# SCH_Satlla_4_Solar_unit_left_2023-01-29.net
KiCad netlist of a schematic drawn in EasyEDA
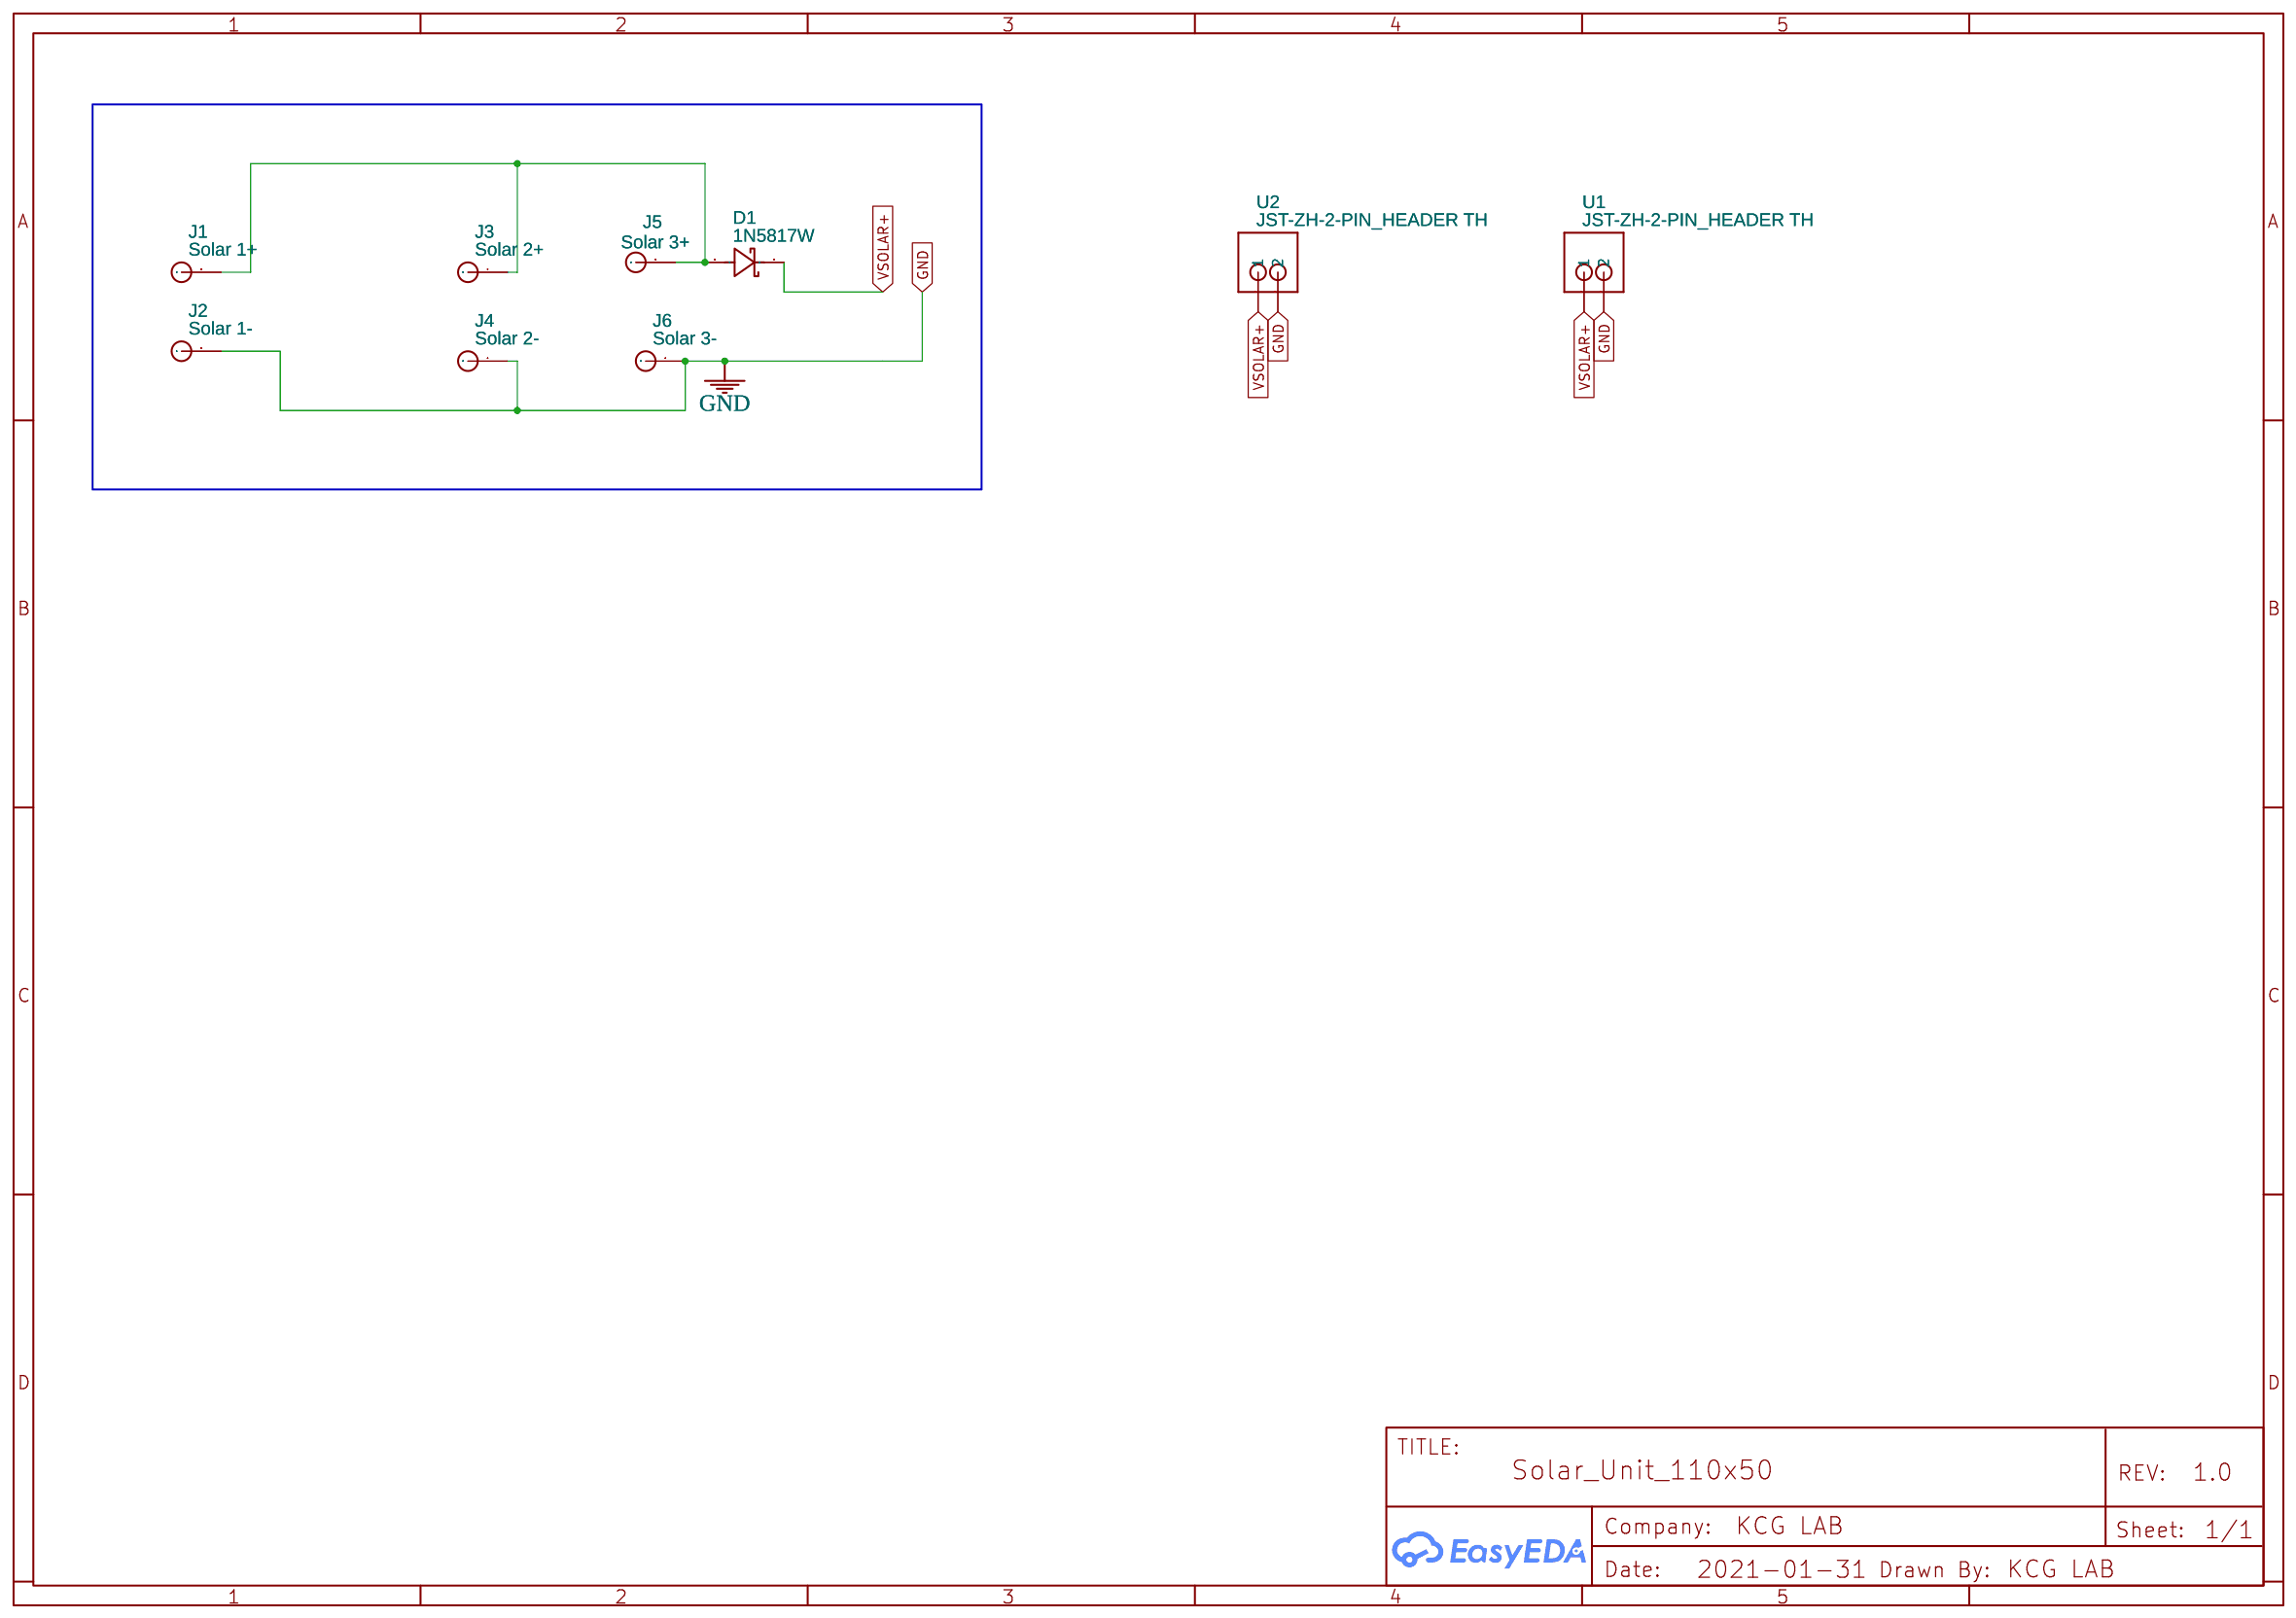
[diagram p0: schematic sheet]

(export (version "E")
  (design (tool "Eeschema 10.0.6"))
  (components
    (comp (ref "D1")
      (value "1N5817W")
      (fields (field (name "BOM_Supplier Part") "C727113"))
      (libsource (lib "") (part "1N5817W"))
    )
    (comp (ref "J1")
      (value "Solar 1+")
      (fields
        (field (name "BOM_Manufacturer Part") "RF130-1013BBS0741")
        (field (name "BOM_Supplier Part") "320030026")
      )
      (libsource (lib "") (part "Connector"))
    )
    (comp (ref "J2")
      (value "Solar 1-")
      (fields
        (field (name "BOM_Manufacturer Part") "RF130-1013BBS0741")
        (field (name "BOM_Supplier Part") "320030026")
      )
      (libsource (lib "") (part "Connector"))
    )
    (comp (ref "J3")
      (value "Solar 2+")
      (fields
        (field (name "BOM_Manufacturer Part") "RF130-1013BBS0741")
        (field (name "BOM_Supplier Part") "320030026")
      )
      (libsource (lib "") (part "Connector"))
    )
    (comp (ref "J4")
      (value "Solar 2-")
      (fields
        (field (name "BOM_Manufacturer Part") "RF130-1013BBS0741")
        (field (name "BOM_Supplier Part") "320030026")
      )
      (libsource (lib "") (part "Connector"))
    )
    (comp (ref "J5")
      (value "Solar 3+")
      (fields
        (field (name "BOM_Manufacturer Part") "RF130-1013BBS0741")
        (field (name "BOM_Supplier Part") "320030026")
      )
      (libsource (lib "") (part "Connector"))
    )
    (comp (ref "J6")
      (value "Solar 3-")
      (fields
        (field (name "BOM_Manufacturer Part") "RF130-1013BBS0741")
        (field (name "BOM_Supplier Part") "320030026")
      )
      (libsource (lib "") (part "Connector"))
    )
    (comp (ref "U1") (value "JST-ZH-2-PIN_HEADER TH") (libsource (lib "") (part "JST-ZH-2-PIN_HEADER TH")))
    (comp (ref "U2") (value "JST-ZH-2-PIN_HEADER TH") (libsource (lib "") (part "JST-ZH-2-PIN_HEADER TH")))
  )
  (nets
    (net (code "1") (name "GND") (class "Default")
      (node (ref "J2") (pin "1") (pinfunction "1_1") (pintype "unspecified"))
      (node (ref "J4") (pin "1") (pinfunction "1_1") (pintype "unspecified"))
      (node (ref "J6") (pin "1") (pinfunction "1_1") (pintype "unspecified"))
      (node (ref "U1") (pin "2") (pinfunction "2_2") (pintype "unspecified"))
      (node (ref "U2") (pin "2") (pinfunction "2_2") (pintype "unspecified"))
    )
    (net (code "2") (name "Net-(D1-A)") (class "Default")
      (node (ref "D1") (pin "2") (pinfunction "A_2") (pintype "unspecified"))
      (node (ref "J1") (pin "1") (pinfunction "1_1") (pintype "unspecified"))
      (node (ref "J3") (pin "1") (pinfunction "1_1") (pintype "unspecified"))
      (node (ref "J5") (pin "1") (pinfunction "1_1") (pintype "unspecified"))
    )
    (net (code "3") (name "VSOLAR+") (class "Default")
      (node (ref "D1") (pin "1") (pinfunction "C_1") (pintype "unspecified"))
      (node (ref "U1") (pin "1") (pinfunction "1_1") (pintype "unspecified"))
      (node (ref "U2") (pin "1") (pinfunction "1_1") (pintype "unspecified"))
    )
  )
)
